# Sheet1-IECA-01-21.net
KiCad netlist of a schematic drawn in Altium Designer
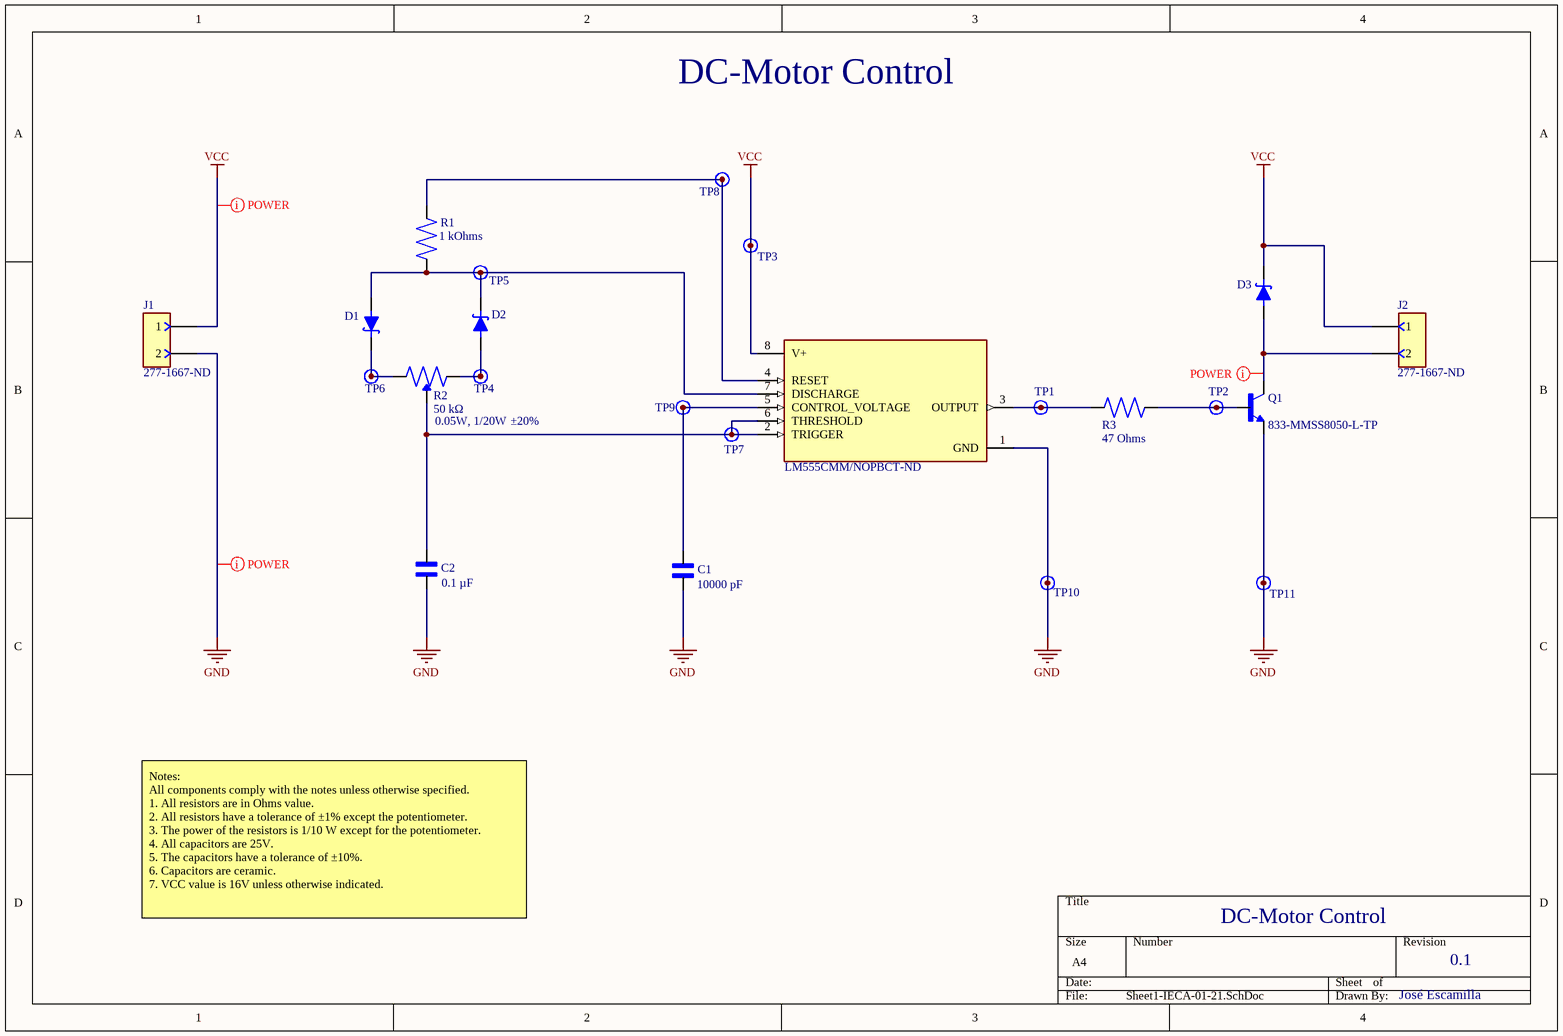
[diagram p0: Sheet1-IECA-01-21.SchDoc]

(export (version "E")
  (design (tool "Eeschema 10.0.6"))
  (components
    (comp (ref "C1")
      (value "10000 pF")
      (footprint "CAP0603_C0603C103K3HACTU")
      (description "10000 pF ±10% 25V Ceramic Capacitor X8R 0603 (1608 Metric).")
      (fields (field (name "MANUFACTURER") "KEMET") (field (name "TOLERANCE") "±10%"))
      (libsource (lib "Schlib1") (part "C0603C103K3HAC7867"))
    )
    (comp (ref "C2")
      (value "0.1 µF")
      (footprint "CAP0603_C0603C104K3RAC7081")
      (description "0.1 µF ±10% 25V Ceramic Capacitor X7R 0603 (1608 Metric).")
      (fields (field (name "MANUFACTURER") "KEMET") (field (name "TOLERANCE") "±10%"))
      (libsource (lib "Schlib1") (part "C0603C104K3RAC7081"))
    )
    (comp (ref "D1")
      (value "SD103CW-FDIDKR-ND")
      (footprint "SD103CW-13-F")
      (description "Diode Schottky 20 V 350mA (DC) Surface Mount SOD-123.")
      (fields (field (name "MANUFACTURER") "Diodes Incorporated"))
      (libsource (lib "Schlib1") (part "SD103CW-13-F"))
    )
    (comp (ref "D2")
      (value "SD103CW-FDIDKR-ND")
      (footprint "SD103CW-13-F")
      (description "Diode Schottky 20 V 350mA (DC) Surface Mount SOD-123.")
      (fields (field (name "MANUFACTURER") "Diodes Incorporated"))
      (libsource (lib "Schlib1") (part "SD103CW-13-F"))
    )
    (comp (ref "D3")
      (value "SD103CW-FDIDKR-ND")
      (footprint "SD103CW-13-F")
      (description "Diode Schottky 20 V 350mA (DC) Surface Mount SOD-123.")
      (fields (field (name "MANUFACTURER") "Diodes Incorporated"))
      (libsource (lib "Schlib1") (part "SD103CW-13-F"))
    )
    (comp (ref "J1")
      (value "277-1667-ND")
      (footprint "TB_2PIN_1935161")
      (description "2 Position Wire to Board Terminal Block Horizontal with Board 0.197\" (5.00mm) Through Hole.")
      (fields
        (field (name "MANUFACTURER") "Phoenix Contact")
        (field (name "VOLTAGE") "300 V")
        (field (name "SUPPLIER PART NUMBER 1") "277-1667-ND")
      )
      (libsource (lib "") (part "1935161_1"))
    )
    (comp (ref "J2")
      (value "277-1667-ND")
      (footprint "TB_2PIN_1935161")
      (description "2 Position Wire to Board Terminal Block Horizontal with Board 0.197\" (5.00mm) Through Hole.")
      (fields
        (field (name "MANUFACTURER") "Phoenix Contact")
        (field (name "VOLTAGE") "300 V")
        (field (name "SUPPLIER PART NUMBER 1") "277-1667-ND")
      )
      (libsource (lib "Schlib1") (part "1935161"))
    )
    (comp (ref "Q1")
      (value "833-MMSS8050-L-TP")
      (footprint "SOT23-MMSS8050-L-TP")
      (description "Bipolar (BJT) Transistor NPN 25 V 1.5 A 100MHz 625 mW Surface Mount SOT-23.")
      (fields
        (field (name "MANUFACTURER") "Micro Commercial Co")
        (field (name "SUPPLIER PART NUMBER 1") "833-MMSS8050-L-TP")
      )
      (libsource (lib "Schlib1") (part "MMSS8050-L-TP"))
    )
    (comp (ref "R1")
      (value "1 kOhms")
      (footprint "RES0603_ERJU03F1001V")
      (fields
        (field (name "TOLERANCE") "±1%")
        (field (name "MANUFACTURER") "Panasonic Electronic Components")
      )
      (libsource (lib "Schlib1") (part "ERJU03F1001V"))
    )
    (comp (ref "R2")
      (value "50 kΩ")
      (footprint "PRS11S-N20F-503B1")
      (description "50k Ohm 1 Gang Linear Surface Mount Potentiometer None 1.0 Kierros Carbon 0.05W, 1/20W Gull Wing.")
      (fields
        (field (name "MANUFACTURER") "Bourns Inc.")
        (field (name "TOLERANCE") "±20%")
        (field (name "POWER (WATTS)") "0.05W, 1/20W")
      )
      (libsource (lib "Schlib1") (part "PRS11S-N20F-503B1"))
    )
    (comp (ref "R3")
      (value "47 Ohms")
      (footprint "RES0603_ERJU03F47R0V")
      (fields
        (field (name "MANUFACTURER") "Panasonic Electronic Components")
        (field (name "TOLERANCE") "±1%")
      )
      (libsource (lib "Schlib1") (part "ERJ-U03F47R0V"))
    )
    (comp (ref "TP1") (value "TP") (footprint "TP") (libsource (lib "Schlib1") (part "TP")))
    (comp (ref "TP2") (value "TP") (footprint "TP") (libsource (lib "Schlib1") (part "TP")))
    (comp (ref "TP3") (value "TP") (footprint "TP") (libsource (lib "Schlib1") (part "TP")))
    (comp (ref "TP4") (value "TP") (footprint "TP") (libsource (lib "Schlib1") (part "TP")))
    (comp (ref "TP5") (value "TP") (footprint "TP") (libsource (lib "Schlib1") (part "TP")))
    (comp (ref "TP6") (value "TP") (footprint "TP") (libsource (lib "Schlib1") (part "TP")))
    (comp (ref "TP7") (value "TP") (footprint "TP") (libsource (lib "Schlib1") (part "TP")))
    (comp (ref "TP8") (value "TP") (footprint "TP") (libsource (lib "Schlib1") (part "TP")))
    (comp (ref "TP9") (value "TP") (footprint "TP") (libsource (lib "Schlib1") (part "TP")))
    (comp (ref "TP10") (value "TP") (footprint "TP") (libsource (lib "Schlib1") (part "TP")))
    (comp (ref "TP11") (value "TP") (footprint "TP") (libsource (lib "Schlib1") (part "TP")))
    (comp (ref "U1")
      (value "LM555CMM/NOPBCT-ND")
      (footprint "LM555SOP65P490X110-8N")
      (description "555 Type, Timer/Oscillator (Single) IC 100kHz 8-VSSOP.")
      (fields
        (field (name "MANUFACTURER") "Texas Instruments")
        (field (name "SUPPLIER PART NUMBER 1") "LM555CMM/NOPBCT-ND")
      )
      (libsource (lib "Schlib1") (part "LM555CMM/NOPB"))
    )
  )
  (nets
    (net (code "1") (name "GND") (class "Default")
      (node (ref "C1") (pin "2") (pinfunction "2_2") (pintype "passive"))
      (node (ref "C2") (pin "2") (pinfunction "2_2") (pintype "passive"))
      (node (ref "J1") (pin "2") (pinfunction "2_2") (pintype "passive"))
      (node (ref "Q1") (pin "2") (pinfunction "E_2") (pintype "passive"))
      (node (ref "TP10") (pin "1") (pinfunction "1_1") (pintype "passive"))
      (node (ref "TP11") (pin "1") (pinfunction "1_1") (pintype "passive"))
      (node (ref "U1") (pin "1") (pinfunction "GND_1") (pintype "power_in"))
    )
    (net (code "2") (name "Net-(D1-K)") (class "Default")
      (node (ref "D1") (pin "C") (pinfunction "K_C") (pintype "passive"))
      (node (ref "R2") (pin "1") (pinfunction "CCW_1") (pintype "passive"))
      (node (ref "TP6") (pin "1") (pinfunction "1_1") (pintype "passive"))
    )
    (net (code "3") (name "Net-(D2-K)") (class "Default")
      (node (ref "D1") (pin "A") (pinfunction "A_A") (pintype "passive"))
      (node (ref "D2") (pin "C") (pinfunction "K_C") (pintype "passive"))
      (node (ref "R1") (pin "1") (pinfunction "1_1") (pintype "passive"))
      (node (ref "TP5") (pin "1") (pinfunction "1_1") (pintype "passive"))
      (node (ref "U1") (pin "7") (pinfunction "DISCHARGE_7") (pintype "input"))
    )
    (net (code "4") (name "Net-(Q1-B)") (class "Default")
      (node (ref "Q1") (pin "1") (pinfunction "B_1") (pintype "passive"))
      (node (ref "R3") (pin "2") (pinfunction "2_2") (pintype "passive"))
      (node (ref "TP2") (pin "1") (pinfunction "1_1") (pintype "passive"))
    )
    (net (code "5") (name "Net-(Q1-C)") (class "Default")
      (node (ref "D3") (pin "A") (pinfunction "A_A") (pintype "passive"))
      (node (ref "J2") (pin "2") (pinfunction "2_2") (pintype "passive"))
      (node (ref "Q1") (pin "3") (pinfunction "C_3") (pintype "passive"))
    )
    (net (code "6") (name "Net-(R2-CW)") (class "Default")
      (node (ref "D2") (pin "A") (pinfunction "A_A") (pintype "passive"))
      (node (ref "R2") (pin "3") (pinfunction "CW_3") (pintype "passive"))
      (node (ref "TP4") (pin "1") (pinfunction "1_1") (pintype "passive"))
    )
    (net (code "7") (name "Net-(R2-W)") (class "Default")
      (node (ref "C2") (pin "1") (pinfunction "1_1") (pintype "passive"))
      (node (ref "R2") (pin "2") (pinfunction "W_2") (pintype "passive"))
      (node (ref "TP7") (pin "1") (pinfunction "1_1") (pintype "passive"))
      (node (ref "U1") (pin "2") (pinfunction "TRIGGER_2") (pintype "input"))
      (node (ref "U1") (pin "6") (pinfunction "THRESHOLD_6") (pintype "input"))
    )
    (net (code "8") (name "Net-(U1-CONTROL_VOLTAGE)") (class "Default")
      (node (ref "C1") (pin "1") (pinfunction "1_1") (pintype "passive"))
      (node (ref "TP9") (pin "1") (pinfunction "1_1") (pintype "passive"))
      (node (ref "U1") (pin "5") (pinfunction "CONTROL_VOLTAGE_5") (pintype "input"))
    )
    (net (code "9") (name "Net-(U1-OUTPUT)") (class "Default")
      (node (ref "R3") (pin "1") (pinfunction "1_1") (pintype "passive"))
      (node (ref "TP1") (pin "1") (pinfunction "1_1") (pintype "passive"))
      (node (ref "U1") (pin "3") (pinfunction "OUTPUT_3") (pintype "output"))
    )
    (net (code "10") (name "Net-(U1-RESET)") (class "Default")
      (node (ref "R1") (pin "2") (pinfunction "2_2") (pintype "passive"))
      (node (ref "TP8") (pin "1") (pinfunction "1_1") (pintype "passive"))
      (node (ref "U1") (pin "4") (pinfunction "RESET_4") (pintype "input"))
    )
    (net (code "11") (name "VCC") (class "Default")
      (node (ref "D3") (pin "C") (pinfunction "K_C") (pintype "passive"))
      (node (ref "J1") (pin "1") (pinfunction "1_1") (pintype "passive"))
      (node (ref "J2") (pin "1") (pinfunction "1_1") (pintype "passive"))
      (node (ref "TP3") (pin "1") (pinfunction "1_1") (pintype "passive"))
      (node (ref "U1") (pin "8") (pinfunction "V+_8") (pintype "power_in"))
    )
  )
)
